# zap-3V.net
KiCad netlist of a schematic drawn in EAGLE
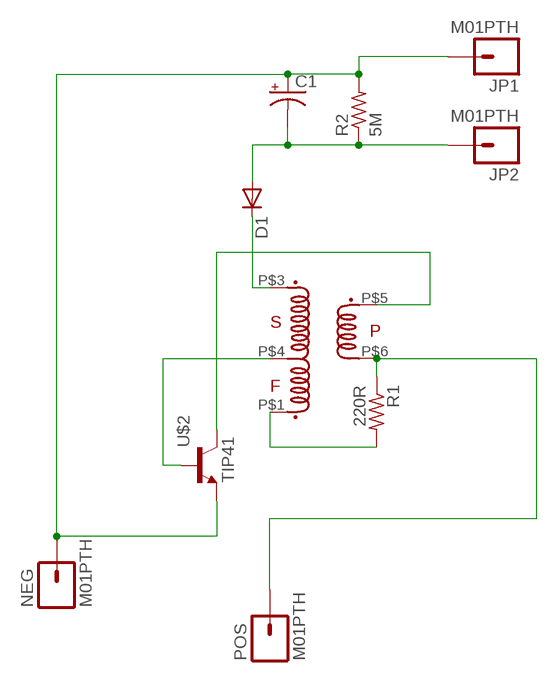
[diagram p0: schematic, sheet 1]

(export (version "E")
  (design (tool "Eeschema 10.0.6"))
  (components
    (comp (ref "C1")
      (value "CAPACITOR_POL")
      (footprint "eagle-import:E5-10,5-SIDE")
      (libsource (lib "eagle-import") (part "CAPACITOR_POL"))
    )
    (comp (ref "D1")
      (value "DIODEPTH")
      (footprint "eagle-import:DIODE-1N4001")
      (libsource (lib "eagle-import") (part "DIODEPTH"))
    )
    (comp (ref "JP1")
      (value "M01PTH")
      (footprint "eagle-import:1X01")
      (libsource (lib "eagle-import") (part "M01PTH"))
    )
    (comp (ref "JP2")
      (value "M01PTH")
      (footprint "eagle-import:1X01")
      (libsource (lib "eagle-import") (part "M01PTH"))
    )
    (comp (ref "NEG")
      (value "M01PTH")
      (footprint "eagle-import:1X01")
      (libsource (lib "eagle-import") (part "M01PTH"))
    )
    (comp (ref "POS")
      (value "M01PTH")
      (footprint "eagle-import:1X01")
      (libsource (lib "eagle-import") (part "M01PTH"))
    )
    (comp (ref "R1")
      (value "220R")
      (footprint "eagle-import:0207_12")
      (libsource (lib "eagle-import") (part "RESISTOR0207/12"))
    )
    (comp (ref "R2")
      (value "5M")
      (footprint "eagle-import:0207_7")
      (libsource (lib "eagle-import") (part "RESISTOR0207/7"))
    )
    (comp (ref "U$1")
      (value "XFT-FLYBACK3V")
      (footprint "eagle-import:XFT-FLYBACK")
      (libsource (lib "eagle-import") (part "XFT-FLYBACK3V"))
    )
    (comp (ref "U$2")
      (value "TIP41")
      (footprint "eagle-import:TO220H")
      (libsource (lib "eagle-import") (part "TIP41"))
    )
  )
  (nets
    (net (code "1") (name "Net-(C1-+)") (class "Default")
      (node (ref "C1") (pin "P$1") (pinfunction "+_P$1") (pintype "passive"))
      (node (ref "JP1") (pin "1") (pinfunction "1_1") (pintype "passive"))
      (node (ref "NEG") (pin "1") (pinfunction "1_1") (pintype "passive"))
      (node (ref "R2") (pin "2") (pinfunction "2_2") (pintype "passive"))
      (node (ref "U$2") (pin "3") (pinfunction "E_3") (pintype "passive"))
    )
    (net (code "2") (name "Net-(C1--)") (class "Default")
      (node (ref "C1") (pin "P$2") (pinfunction "-_P$2") (pintype "passive"))
      (node (ref "D1") (pin "A") (pinfunction "A_A") (pintype "passive"))
      (node (ref "JP2") (pin "1") (pinfunction "1_1") (pintype "passive"))
      (node (ref "R2") (pin "1") (pinfunction "1_1") (pintype "passive"))
    )
    (net (code "3") (name "Net-(U$1-P$1.S)") (class "Default")
      (node (ref "D1") (pin "C") (pinfunction "C_C") (pintype "passive"))
      (node (ref "U$1") (pin "P$3") (pinfunction "P$1.S_P$3") (pintype "passive"))
    )
    (net (code "4") (name "Net-(U$1-P$2.CENTRE)") (class "Default")
      (node (ref "U$1") (pin "P$4") (pinfunction "P$2.CENTRE_P$4") (pintype "passive"))
      (node (ref "U$2") (pin "1") (pinfunction "B_1") (pintype "passive"))
    )
    (net (code "5") (name "Net-(U$1-P$3.F)") (class "Default")
      (node (ref "R1") (pin "2") (pinfunction "2_2") (pintype "passive"))
      (node (ref "U$1") (pin "P$1") (pinfunction "P$3.F_P$1") (pintype "passive"))
    )
    (net (code "6") (name "Net-(U$1-P$4.P1)") (class "Default")
      (node (ref "U$1") (pin "P$5") (pinfunction "P$4.P1_P$5") (pintype "passive"))
      (node (ref "U$2") (pin "2") (pinfunction "C_2") (pintype "passive"))
    )
    (net (code "7") (name "Net-(U$1-P$5.P2)") (class "Default")
      (node (ref "POS") (pin "1") (pinfunction "1_1") (pintype "passive"))
      (node (ref "R1") (pin "1") (pinfunction "1_1") (pintype "passive"))
      (node (ref "U$1") (pin "P$6") (pinfunction "P$5.P2_P$6") (pintype "passive"))
    )
  )
)
